# main_schematic.net
KiCad netlist of a schematic drawn in Altium Designer
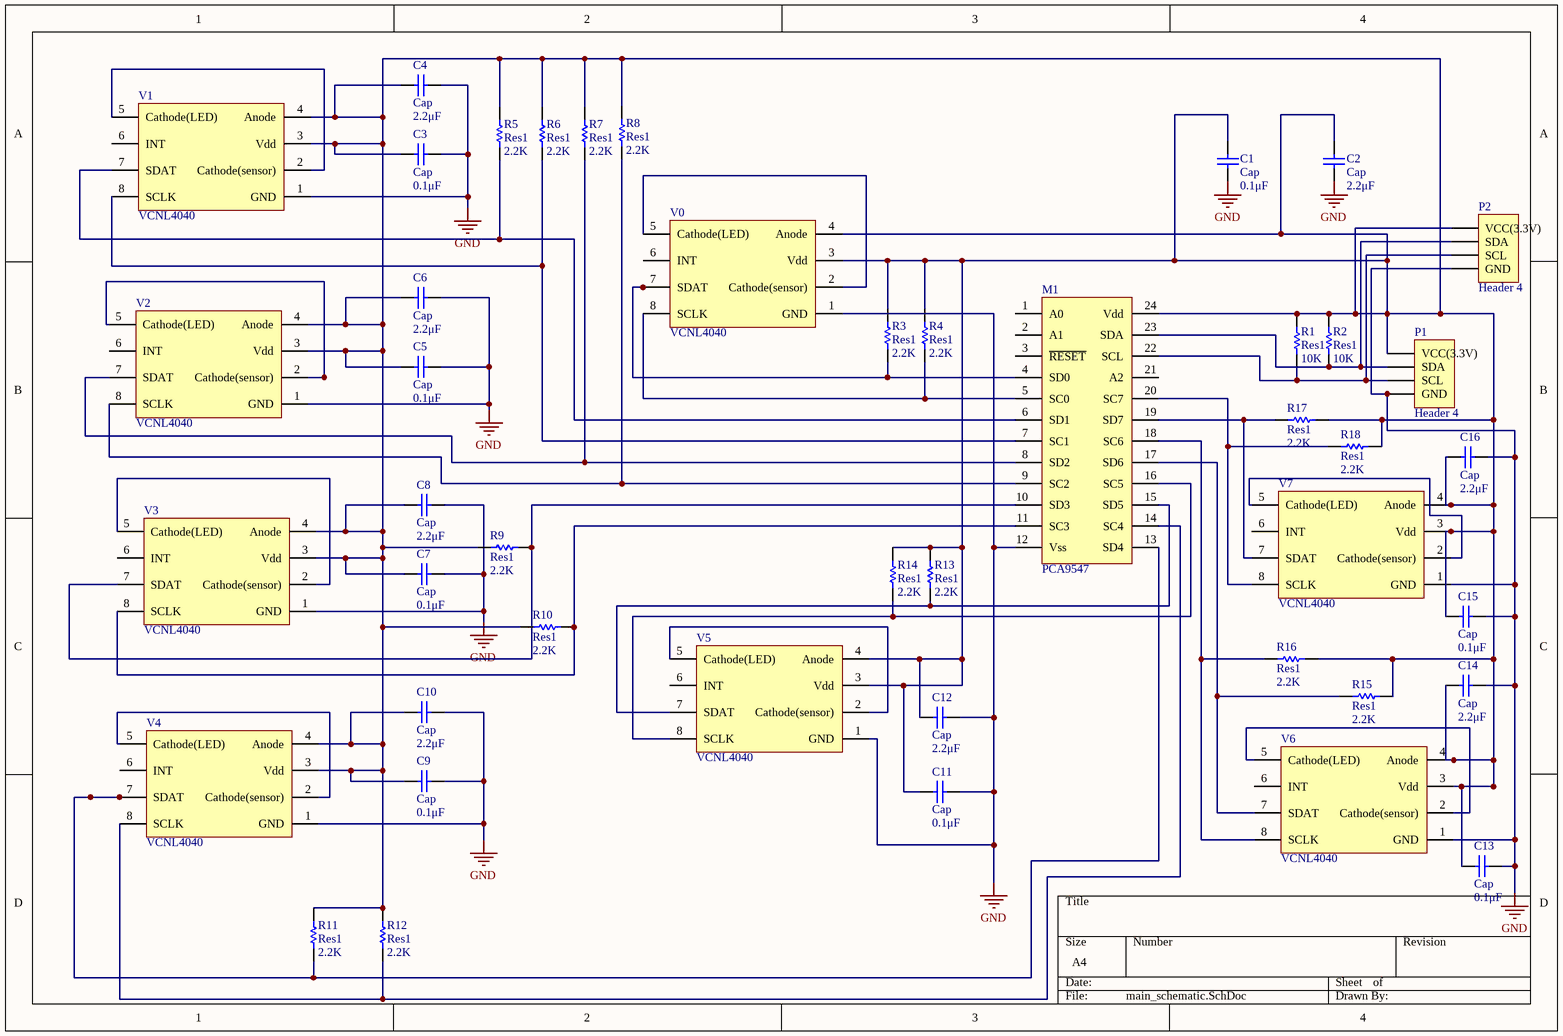
[diagram p0: main_schematic.SchDoc]

(export (version "E")
  (design (tool "Eeschema 10.0.6"))
  (components
    (comp (ref "C1")
      (value "Cap")
      (footprint "1608[0603]")
      (description "Capacitor")
      (fields (field (name "ALTIUM_VALUE") "0.1μF") (field (name "PUBLISHER") "Altium Limited"))
      (libsource (lib "Miscellaneous Devices") (part "Cap"))
    )
    (comp (ref "C2")
      (value "Cap")
      (footprint "1608[0603]")
      (description "Capacitor")
      (fields (field (name "ALTIUM_VALUE") "2.2μF") (field (name "PUBLISHER") "Altium Limited"))
      (libsource (lib "Miscellaneous Devices") (part "Cap"))
    )
    (comp (ref "C3")
      (value "Cap")
      (footprint "1608[0603]")
      (description "Capacitor")
      (fields (field (name "ALTIUM_VALUE") "0.1μF") (field (name "PUBLISHER") "Altium Limited"))
      (libsource (lib "Miscellaneous Devices") (part "Cap"))
    )
    (comp (ref "C4")
      (value "Cap")
      (footprint "1608[0603]")
      (description "Capacitor")
      (fields (field (name "ALTIUM_VALUE") "2.2μF") (field (name "PUBLISHER") "Altium Limited"))
      (libsource (lib "Miscellaneous Devices") (part "Cap"))
    )
    (comp (ref "C5")
      (value "Cap")
      (footprint "1608[0603]")
      (description "Capacitor")
      (fields (field (name "ALTIUM_VALUE") "0.1μF") (field (name "PUBLISHER") "Altium Limited"))
      (libsource (lib "Miscellaneous Devices") (part "Cap"))
    )
    (comp (ref "C6")
      (value "Cap")
      (footprint "1608[0603]")
      (description "Capacitor")
      (fields (field (name "ALTIUM_VALUE") "2.2μF") (field (name "PUBLISHER") "Altium Limited"))
      (libsource (lib "Miscellaneous Devices") (part "Cap"))
    )
    (comp (ref "C7")
      (value "Cap")
      (footprint "1608[0603]")
      (description "Capacitor")
      (fields (field (name "ALTIUM_VALUE") "0.1μF") (field (name "PUBLISHER") "Altium Limited"))
      (libsource (lib "Miscellaneous Devices") (part "Cap"))
    )
    (comp (ref "C8")
      (value "Cap")
      (footprint "1608[0603]")
      (description "Capacitor")
      (fields (field (name "ALTIUM_VALUE") "2.2μF") (field (name "PUBLISHER") "Altium Limited"))
      (libsource (lib "Miscellaneous Devices") (part "Cap"))
    )
    (comp (ref "C9")
      (value "Cap")
      (footprint "1608[0603]")
      (description "Capacitor")
      (fields (field (name "ALTIUM_VALUE") "0.1μF") (field (name "PUBLISHER") "Altium Limited"))
      (libsource (lib "Miscellaneous Devices") (part "Cap"))
    )
    (comp (ref "C10")
      (value "Cap")
      (footprint "1608[0603]")
      (description "Capacitor")
      (fields (field (name "ALTIUM_VALUE") "2.2μF") (field (name "PUBLISHER") "Altium Limited"))
      (libsource (lib "Miscellaneous Devices") (part "Cap"))
    )
    (comp (ref "C11")
      (value "Cap")
      (footprint "1608[0603]")
      (description "Capacitor")
      (fields (field (name "ALTIUM_VALUE") "0.1μF") (field (name "PUBLISHER") "Altium Limited"))
      (libsource (lib "Miscellaneous Devices") (part "Cap"))
    )
    (comp (ref "C12")
      (value "Cap")
      (footprint "1608[0603]")
      (description "Capacitor")
      (fields (field (name "ALTIUM_VALUE") "2.2μF") (field (name "PUBLISHER") "Altium Limited"))
      (libsource (lib "Miscellaneous Devices") (part "Cap"))
    )
    (comp (ref "C13")
      (value "Cap")
      (footprint "1608[0603]")
      (description "Capacitor")
      (fields (field (name "ALTIUM_VALUE") "0.1μF") (field (name "PUBLISHER") "Altium Limited"))
      (libsource (lib "Miscellaneous Devices") (part "Cap"))
    )
    (comp (ref "C14")
      (value "Cap")
      (footprint "1608[0603]")
      (description "Capacitor")
      (fields (field (name "ALTIUM_VALUE") "2.2μF") (field (name "PUBLISHER") "Altium Limited"))
      (libsource (lib "Miscellaneous Devices") (part "Cap"))
    )
    (comp (ref "C15")
      (value "Cap")
      (footprint "1608[0603]")
      (description "Capacitor")
      (fields (field (name "ALTIUM_VALUE") "0.1μF") (field (name "PUBLISHER") "Altium Limited"))
      (libsource (lib "Miscellaneous Devices") (part "Cap"))
    )
    (comp (ref "C16")
      (value "Cap")
      (footprint "1608[0603]")
      (description "Capacitor")
      (fields (field (name "ALTIUM_VALUE") "2.2μF") (field (name "PUBLISHER") "Altium Limited"))
      (libsource (lib "Miscellaneous Devices") (part "Cap"))
    )
    (comp (ref "M1") (value "PCA9547") (footprint "TSSOP24") (libsource (lib "PCA9547") (part "PCA9547")))
    (comp (ref "P1")
      (value "Header 4")
      (footprint "HDR1X4")
      (description "Header, 4-Pin")
      (fields (field (name "PUBLISHER") "Altium Limited"))
      (libsource (lib "Miscellaneous Connectors") (part "Header 4"))
    )
    (comp (ref "P2")
      (value "Header 4")
      (footprint "HDR1X4")
      (description "Header, 4-Pin")
      (fields (field (name "PUBLISHER") "Altium Limited"))
      (libsource (lib "Miscellaneous Connectors") (part "Header 4"))
    )
    (comp (ref "R1")
      (value "Res1")
      (footprint "1608[0603]")
      (description "Resistor")
      (fields (field (name "ALTIUM_VALUE") "10K") (field (name "PUBLISHER") "Altium Limited"))
      (libsource (lib "Miscellaneous Devices") (part "Res1"))
    )
    (comp (ref "R2")
      (value "Res1")
      (footprint "1608[0603]")
      (description "Resistor")
      (fields (field (name "ALTIUM_VALUE") "10K") (field (name "PUBLISHER") "Altium Limited"))
      (libsource (lib "Miscellaneous Devices") (part "Res1"))
    )
    (comp (ref "R3")
      (value "Res1")
      (footprint "1608[0603]")
      (description "Resistor")
      (fields (field (name "ALTIUM_VALUE") "2.2K") (field (name "PUBLISHER") "Altium Limited"))
      (libsource (lib "Miscellaneous Devices") (part "Res1"))
    )
    (comp (ref "R4")
      (value "Res1")
      (footprint "1608[0603]")
      (description "Resistor")
      (fields (field (name "ALTIUM_VALUE") "2.2K") (field (name "PUBLISHER") "Altium Limited"))
      (libsource (lib "Miscellaneous Devices") (part "Res1"))
    )
    (comp (ref "R5")
      (value "Res1")
      (footprint "1608[0603]")
      (description "Resistor")
      (fields (field (name "ALTIUM_VALUE") "2.2K") (field (name "PUBLISHER") "Altium Limited"))
      (libsource (lib "Miscellaneous Devices") (part "Res1"))
    )
    (comp (ref "R6")
      (value "Res1")
      (footprint "1608[0603]")
      (description "Resistor")
      (fields (field (name "ALTIUM_VALUE") "2.2K") (field (name "PUBLISHER") "Altium Limited"))
      (libsource (lib "Miscellaneous Devices") (part "Res1"))
    )
    (comp (ref "R7")
      (value "Res1")
      (footprint "1608[0603]")
      (description "Resistor")
      (fields (field (name "ALTIUM_VALUE") "2.2K") (field (name "PUBLISHER") "Altium Limited"))
      (libsource (lib "Miscellaneous Devices") (part "Res1"))
    )
    (comp (ref "R8")
      (value "Res1")
      (footprint "1608[0603]")
      (description "Resistor")
      (fields (field (name "ALTIUM_VALUE") "2.2K") (field (name "PUBLISHER") "Altium Limited"))
      (libsource (lib "Miscellaneous Devices") (part "Res1"))
    )
    (comp (ref "R9")
      (value "Res1")
      (footprint "1608[0603]")
      (description "Resistor")
      (fields (field (name "ALTIUM_VALUE") "2.2K") (field (name "PUBLISHER") "Altium Limited"))
      (libsource (lib "Miscellaneous Devices") (part "Res1"))
    )
    (comp (ref "R10")
      (value "Res1")
      (footprint "1608[0603]")
      (description "Resistor")
      (fields (field (name "ALTIUM_VALUE") "2.2K") (field (name "PUBLISHER") "Altium Limited"))
      (libsource (lib "Miscellaneous Devices") (part "Res1"))
    )
    (comp (ref "R11")
      (value "Res1")
      (footprint "1608[0603]")
      (description "Resistor")
      (fields (field (name "ALTIUM_VALUE") "2.2K") (field (name "PUBLISHER") "Altium Limited"))
      (libsource (lib "Miscellaneous Devices") (part "Res1"))
    )
    (comp (ref "R12")
      (value "Res1")
      (footprint "1608[0603]")
      (description "Resistor")
      (fields (field (name "ALTIUM_VALUE") "2.2K") (field (name "PUBLISHER") "Altium Limited"))
      (libsource (lib "Miscellaneous Devices") (part "Res1"))
    )
    (comp (ref "R13")
      (value "Res1")
      (footprint "1608[0603]")
      (description "Resistor")
      (fields (field (name "ALTIUM_VALUE") "2.2K") (field (name "PUBLISHER") "Altium Limited"))
      (libsource (lib "Miscellaneous Devices") (part "Res1"))
    )
    (comp (ref "R14")
      (value "Res1")
      (footprint "1608[0603]")
      (description "Resistor")
      (fields (field (name "ALTIUM_VALUE") "2.2K") (field (name "PUBLISHER") "Altium Limited"))
      (libsource (lib "Miscellaneous Devices") (part "Res1"))
    )
    (comp (ref "R15")
      (value "Res1")
      (footprint "1608[0603]")
      (description "Resistor")
      (fields (field (name "ALTIUM_VALUE") "2.2K") (field (name "PUBLISHER") "Altium Limited"))
      (libsource (lib "Miscellaneous Devices") (part "Res1"))
    )
    (comp (ref "R16")
      (value "Res1")
      (footprint "1608[0603]")
      (description "Resistor")
      (fields (field (name "ALTIUM_VALUE") "2.2K") (field (name "PUBLISHER") "Altium Limited"))
      (libsource (lib "Miscellaneous Devices") (part "Res1"))
    )
    (comp (ref "R17")
      (value "Res1")
      (footprint "1608[0603]")
      (description "Resistor")
      (fields (field (name "ALTIUM_VALUE") "2.2K") (field (name "PUBLISHER") "Altium Limited"))
      (libsource (lib "Miscellaneous Devices") (part "Res1"))
    )
    (comp (ref "R18")
      (value "Res1")
      (footprint "1608[0603]")
      (description "Resistor")
      (fields (field (name "ALTIUM_VALUE") "2.2K") (field (name "PUBLISHER") "Altium Limited"))
      (libsource (lib "Miscellaneous Devices") (part "Res1"))
    )
    (comp (ref "V0") (value "VCNL4040") (footprint "SOP8") (libsource (lib "VCNL4040") (part "Component_1")))
    (comp (ref "V1") (value "VCNL4040") (footprint "SOP8") (libsource (lib "VCNL4040") (part "Component_1")))
    (comp (ref "V2") (value "VCNL4040") (footprint "SOP8") (libsource (lib "VCNL4040") (part "Component_1")))
    (comp (ref "V3") (value "VCNL4040") (footprint "SOP8") (libsource (lib "VCNL4040") (part "Component_1")))
    (comp (ref "V4") (value "VCNL4040") (footprint "SOP8") (libsource (lib "VCNL4040") (part "Component_1")))
    (comp (ref "V5") (value "VCNL4040") (footprint "SOP8") (libsource (lib "VCNL4040") (part "Component_1")))
    (comp (ref "V6") (value "VCNL4040") (footprint "SOP8") (libsource (lib "VCNL4040") (part "Component_1")))
    (comp (ref "V7") (value "VCNL4040") (footprint "SOP8") (libsource (lib "VCNL4040") (part "Component_1")))
  )
  (nets
    (net (code "1") (name "GND") (class "Default")
      (node (ref "C1") (pin "1") (pinfunction "1_1") (pintype "passive"))
      (node (ref "C10") (pin "1") (pinfunction "1_1") (pintype "passive"))
      (node (ref "C11") (pin "1") (pinfunction "1_1") (pintype "passive"))
      (node (ref "C12") (pin "1") (pinfunction "1_1") (pintype "passive"))
      (node (ref "C13") (pin "1") (pinfunction "1_1") (pintype "passive"))
      (node (ref "C14") (pin "1") (pinfunction "1_1") (pintype "passive"))
      (node (ref "C15") (pin "1") (pinfunction "1_1") (pintype "passive"))
      (node (ref "C16") (pin "1") (pinfunction "1_1") (pintype "passive"))
      (node (ref "C2") (pin "1") (pinfunction "1_1") (pintype "passive"))
      (node (ref "C3") (pin "1") (pinfunction "1_1") (pintype "passive"))
      (node (ref "C4") (pin "1") (pinfunction "1_1") (pintype "passive"))
      (node (ref "C5") (pin "1") (pinfunction "1_1") (pintype "passive"))
      (node (ref "C6") (pin "1") (pinfunction "1_1") (pintype "passive"))
      (node (ref "C7") (pin "1") (pinfunction "1_1") (pintype "passive"))
      (node (ref "C8") (pin "1") (pinfunction "1_1") (pintype "passive"))
      (node (ref "C9") (pin "1") (pinfunction "1_1") (pintype "passive"))
      (node (ref "M1") (pin "12") (pinfunction "Vss_12") (pintype "passive"))
      (node (ref "P1") (pin "4") (pinfunction "GND_4") (pintype "power_in"))
      (node (ref "P2") (pin "4") (pinfunction "GND_4") (pintype "power_in"))
      (node (ref "V0") (pin "1") (pinfunction "GND_1") (pintype "passive"))
      (node (ref "V1") (pin "1") (pinfunction "GND_1") (pintype "passive"))
      (node (ref "V2") (pin "1") (pinfunction "GND_1") (pintype "passive"))
      (node (ref "V3") (pin "1") (pinfunction "GND_1") (pintype "passive"))
      (node (ref "V4") (pin "1") (pinfunction "GND_1") (pintype "passive"))
      (node (ref "V5") (pin "1") (pinfunction "GND_1") (pintype "passive"))
      (node (ref "V6") (pin "1") (pinfunction "GND_1") (pintype "passive"))
      (node (ref "V7") (pin "1") (pinfunction "GND_1") (pintype "passive"))
    )
    (net (code "2") (name "Net-(M1-SC0)") (class "Default")
      (node (ref "M1") (pin "5") (pinfunction "SC0_5") (pintype "passive"))
      (node (ref "R4") (pin "1") (pinfunction "1_1") (pintype "passive"))
      (node (ref "V0") (pin "8") (pinfunction "SCLK_8") (pintype "passive"))
    )
    (net (code "3") (name "Net-(M1-SC1)") (class "Default")
      (node (ref "M1") (pin "7") (pinfunction "SC1_7") (pintype "passive"))
      (node (ref "R6") (pin "1") (pinfunction "1_1") (pintype "passive"))
      (node (ref "V1") (pin "8") (pinfunction "SCLK_8") (pintype "passive"))
    )
    (net (code "4") (name "Net-(M1-SC2)") (class "Default")
      (node (ref "M1") (pin "9") (pinfunction "SC2_9") (pintype "passive"))
      (node (ref "R8") (pin "1") (pinfunction "1_1") (pintype "passive"))
      (node (ref "V2") (pin "8") (pinfunction "SCLK_8") (pintype "passive"))
    )
    (net (code "5") (name "Net-(M1-SC3)") (class "Default")
      (node (ref "M1") (pin "11") (pinfunction "SC3_11") (pintype "passive"))
      (node (ref "R10") (pin "1") (pinfunction "1_1") (pintype "passive"))
      (node (ref "V3") (pin "8") (pinfunction "SCLK_8") (pintype "passive"))
    )
    (net (code "6") (name "Net-(M1-SC4)") (class "Default")
      (node (ref "M1") (pin "14") (pinfunction "SC4_14") (pintype "passive"))
      (node (ref "R12") (pin "2") (pinfunction "2_2") (pintype "passive"))
      (node (ref "V4") (pin "8") (pinfunction "SCLK_8") (pintype "passive"))
    )
    (net (code "7") (name "Net-(M1-SC5)") (class "Default")
      (node (ref "M1") (pin "16") (pinfunction "SC5_16") (pintype "passive"))
      (node (ref "R14") (pin "1") (pinfunction "1_1") (pintype "passive"))
      (node (ref "V5") (pin "8") (pinfunction "SCLK_8") (pintype "passive"))
    )
    (net (code "8") (name "Net-(M1-SC6)") (class "Default")
      (node (ref "M1") (pin "18") (pinfunction "SC6_18") (pintype "passive"))
      (node (ref "R16") (pin "2") (pinfunction "2_2") (pintype "passive"))
      (node (ref "V6") (pin "8") (pinfunction "SCLK_8") (pintype "passive"))
    )
    (net (code "9") (name "Net-(M1-SC7)") (class "Default")
      (node (ref "M1") (pin "20") (pinfunction "SC7_20") (pintype "passive"))
      (node (ref "R18") (pin "2") (pinfunction "2_2") (pintype "passive"))
      (node (ref "V7") (pin "8") (pinfunction "SCLK_8") (pintype "passive"))
    )
    (net (code "10") (name "Net-(M1-SCL)") (class "Default")
      (node (ref "M1") (pin "22") (pinfunction "SCL_22") (pintype "passive"))
      (node (ref "P1") (pin "3") (pinfunction "SCL_3") (pintype "passive"))
      (node (ref "P2") (pin "3") (pinfunction "SCL_3") (pintype "passive"))
      (node (ref "R1") (pin "1") (pinfunction "1_1") (pintype "passive"))
    )
    (net (code "11") (name "Net-(M1-SD0)") (class "Default")
      (node (ref "M1") (pin "4") (pinfunction "SD0_4") (pintype "passive"))
      (node (ref "R3") (pin "1") (pinfunction "1_1") (pintype "passive"))
      (node (ref "V0") (pin "7") (pinfunction "SDAT_7") (pintype "passive"))
    )
    (net (code "12") (name "Net-(M1-SD1)") (class "Default")
      (node (ref "M1") (pin "6") (pinfunction "SD1_6") (pintype "passive"))
      (node (ref "R5") (pin "1") (pinfunction "1_1") (pintype "passive"))
      (node (ref "V1") (pin "7") (pinfunction "SDAT_7") (pintype "passive"))
    )
    (net (code "13") (name "Net-(M1-SD2)") (class "Default")
      (node (ref "M1") (pin "8") (pinfunction "SD2_8") (pintype "passive"))
      (node (ref "R7") (pin "1") (pinfunction "1_1") (pintype "passive"))
      (node (ref "V2") (pin "7") (pinfunction "SDAT_7") (pintype "passive"))
    )
    (net (code "14") (name "Net-(M1-SD3)") (class "Default")
      (node (ref "M1") (pin "10") (pinfunction "SD3_10") (pintype "passive"))
      (node (ref "R9") (pin "1") (pinfunction "1_1") (pintype "passive"))
      (node (ref "V3") (pin "7") (pinfunction "SDAT_7") (pintype "passive"))
    )
    (net (code "15") (name "Net-(M1-SD4)") (class "Default")
      (node (ref "M1") (pin "13") (pinfunction "SD4_13") (pintype "passive"))
      (node (ref "R11") (pin "2") (pinfunction "2_2") (pintype "passive"))
      (node (ref "V4") (pin "7") (pinfunction "SDAT_7") (pintype "passive"))
    )
    (net (code "16") (name "Net-(M1-SD5)") (class "Default")
      (node (ref "M1") (pin "15") (pinfunction "SD5_15") (pintype "passive"))
      (node (ref "R13") (pin "1") (pinfunction "1_1") (pintype "passive"))
      (node (ref "V5") (pin "7") (pinfunction "SDAT_7") (pintype "passive"))
    )
    (net (code "17") (name "Net-(M1-SD6)") (class "Default")
      (node (ref "M1") (pin "17") (pinfunction "SD6_17") (pintype "passive"))
      (node (ref "R15") (pin "2") (pinfunction "2_2") (pintype "passive"))
      (node (ref "V6") (pin "7") (pinfunction "SDAT_7") (pintype "passive"))
    )
    (net (code "18") (name "Net-(M1-SD7)") (class "Default")
      (node (ref "M1") (pin "19") (pinfunction "SD7_19") (pintype "passive"))
      (node (ref "R17") (pin "2") (pinfunction "2_2") (pintype "passive"))
      (node (ref "V7") (pin "7") (pinfunction "SDAT_7") (pintype "passive"))
    )
    (net (code "19") (name "Net-(M1-SDA)") (class "Default")
      (node (ref "M1") (pin "23") (pinfunction "SDA_23") (pintype "passive"))
      (node (ref "P1") (pin "2") (pinfunction "SDA_2") (pintype "passive"))
      (node (ref "P2") (pin "2") (pinfunction "SDA_2") (pintype "passive"))
      (node (ref "R2") (pin "1") (pinfunction "1_1") (pintype "passive"))
    )
    (net (code "20") (name "Net-(M1-Vdd)") (class "Default")
      (node (ref "C1") (pin "2") (pinfunction "2_2") (pintype "passive"))
      (node (ref "C10") (pin "2") (pinfunction "2_2") (pintype "passive"))
      (node (ref "C11") (pin "2") (pinfunction "2_2") (pintype "passive"))
      (node (ref "C12") (pin "2") (pinfunction "2_2") (pintype "passive"))
      (node (ref "C13") (pin "2") (pinfunction "2_2") (pintype "passive"))
      (node (ref "C14") (pin "2") (pinfunction "2_2") (pintype "passive"))
      (node (ref "C15") (pin "2") (pinfunction "2_2") (pintype "passive"))
      (node (ref "C16") (pin "2") (pinfunction "2_2") (pintype "passive"))
      (node (ref "C2") (pin "2") (pinfunction "2_2") (pintype "passive"))
      (node (ref "C3") (pin "2") (pinfunction "2_2") (pintype "passive"))
      (node (ref "C4") (pin "2") (pinfunction "2_2") (pintype "passive"))
      (node (ref "C5") (pin "2") (pinfunction "2_2") (pintype "passive"))
      (node (ref "C6") (pin "2") (pinfunction "2_2") (pintype "passive"))
      (node (ref "C7") (pin "2") (pinfunction "2_2") (pintype "passive"))
      (node (ref "C8") (pin "2") (pinfunction "2_2") (pintype "passive"))
      (node (ref "C9") (pin "2") (pinfunction "2_2") (pintype "passive"))
      (node (ref "M1") (pin "24") (pinfunction "Vdd_24") (pintype "passive"))
      (node (ref "P1") (pin "1") (pinfunction "VCC(3.3V)_1") (pintype "power_in"))
      (node (ref "P2") (pin "1") (pinfunction "VCC(3.3V)_1") (pintype "power_in"))
      (node (ref "R1") (pin "2") (pinfunction "2_2") (pintype "passive"))
      (node (ref "R10") (pin "2") (pinfunction "2_2") (pintype "passive"))
      (node (ref "R11") (pin "1") (pinfunction "1_1") (pintype "passive"))
      (node (ref "R12") (pin "1") (pinfunction "1_1") (pintype "passive"))
      (node (ref "R13") (pin "2") (pinfunction "2_2") (pintype "passive"))
      (node (ref "R14") (pin "2") (pinfunction "2_2") (pintype "passive"))
      (node (ref "R15") (pin "1") (pinfunction "1_1") (pintype "passive"))
      (node (ref "R16") (pin "1") (pinfunction "1_1") (pintype "passive"))
      (node (ref "R17") (pin "1") (pinfunction "1_1") (pintype "passive"))
      (node (ref "R18") (pin "1") (pinfunction "1_1") (pintype "passive"))
      (node (ref "R2") (pin "2") (pinfunction "2_2") (pintype "passive"))
      (node (ref "R3") (pin "2") (pinfunction "2_2") (pintype "passive"))
      (node (ref "R4") (pin "2") (pinfunction "2_2") (pintype "passive"))
      (node (ref "R5") (pin "2") (pinfunction "2_2") (pintype "passive"))
      (node (ref "R6") (pin "2") (pinfunction "2_2") (pintype "passive"))
      (node (ref "R7") (pin "2") (pinfunction "2_2") (pintype "passive"))
      (node (ref "R8") (pin "2") (pinfunction "2_2") (pintype "passive"))
      (node (ref "R9") (pin "2") (pinfunction "2_2") (pintype "passive"))
      (node (ref "V0") (pin "3") (pinfunction "Vdd_3") (pintype "passive"))
      (node (ref "V0") (pin "4") (pinfunction "Anode_4") (pintype "passive"))
      (node (ref "V1") (pin "3") (pinfunction "Vdd_3") (pintype "passive"))
      (node (ref "V1") (pin "4") (pinfunction "Anode_4") (pintype "passive"))
      (node (ref "V2") (pin "3") (pinfunction "Vdd_3") (pintype "passive"))
      (node (ref "V2") (pin "4") (pinfunction "Anode_4") (pintype "passive"))
      (node (ref "V3") (pin "3") (pinfunction "Vdd_3") (pintype "passive"))
      (node (ref "V3") (pin "4") (pinfunction "Anode_4") (pintype "passive"))
      (node (ref "V4") (pin "3") (pinfunction "Vdd_3") (pintype "passive"))
      (node (ref "V4") (pin "4") (pinfunction "Anode_4") (pintype "passive"))
      (node (ref "V5") (pin "3") (pinfunction "Vdd_3") (pintype "passive"))
      (node (ref "V5") (pin "4") (pinfunction "Anode_4") (pintype "passive"))
      (node (ref "V6") (pin "3") (pinfunction "Vdd_3") (pintype "passive"))
      (node (ref "V6") (pin "4") (pinfunction "Anode_4") (pintype "passive"))
      (node (ref "V7") (pin "3") (pinfunction "Vdd_3") (pintype "passive"))
      (node (ref "V7") (pin "4") (pinfunction "Anode_4") (pintype "passive"))
    )
    (net (code "21") (name "Net-(V0-Cathode(LED))") (class "Default")
      (node (ref "V0") (pin "2") (pinfunction "Cathode(sensor)_2") (pintype "passive"))
      (node (ref "V0") (pin "5") (pinfunction "Cathode(LED)_5") (pintype "passive"))
    )
    (net (code "22") (name "Net-(V1-Cathode(LED))") (class "Default")
      (node (ref "V1") (pin "2") (pinfunction "Cathode(sensor)_2") (pintype "passive"))
      (node (ref "V1") (pin "5") (pinfunction "Cathode(LED)_5") (pintype "passive"))
    )
    (net (code "23") (name "Net-(V2-Cathode(LED))") (class "Default")
      (node (ref "V2") (pin "2") (pinfunction "Cathode(sensor)_2") (pintype "passive"))
      (node (ref "V2") (pin "5") (pinfunction "Cathode(LED)_5") (pintype "passive"))
    )
    (net (code "24") (name "Net-(V3-Cathode(LED))") (class "Default")
      (node (ref "V3") (pin "2") (pinfunction "Cathode(sensor)_2") (pintype "passive"))
      (node (ref "V3") (pin "5") (pinfunction "Cathode(LED)_5") (pintype "passive"))
    )
    (net (code "25") (name "Net-(V4-Cathode(LED))") (class "Default")
      (node (ref "V4") (pin "2") (pinfunction "Cathode(sensor)_2") (pintype "passive"))
      (node (ref "V4") (pin "5") (pinfunction "Cathode(LED)_5") (pintype "passive"))
    )
    (net (code "26") (name "Net-(V5-Cathode(LED))") (class "Default")
      (node (ref "V5") (pin "2") (pinfunction "Cathode(sensor)_2") (pintype "passive"))
      (node (ref "V5") (pin "5") (pinfunction "Cathode(LED)_5") (pintype "passive"))
    )
    (net (code "27") (name "Net-(V6-Cathode(LED))") (class "Default")
      (node (ref "V6") (pin "2") (pinfunction "Cathode(sensor)_2") (pintype "passive"))
      (node (ref "V6") (pin "5") (pinfunction "Cathode(LED)_5") (pintype "passive"))
    )
    (net (code "28") (name "Net-(V7-Cathode(LED))") (class "Default")
      (node (ref "V7") (pin "2") (pinfunction "Cathode(sensor)_2") (pintype "passive"))
      (node (ref "V7") (pin "5") (pinfunction "Cathode(LED)_5") (pintype "passive"))
    )
    (net (code "29") (name "unconnected-(M1-A0-Pad1)") (class "Default")
      (node (ref "M1") (pin "1") (pinfunction "A0_1") (pintype "passive"))
    )
    (net (code "30") (name "unconnected-(M1-A1-Pad2)") (class "Default")
      (node (ref "M1") (pin "2") (pinfunction "A1_2") (pintype "passive"))
    )
    (net (code "31") (name "unconnected-(M1-A2-Pad21)") (class "Default")
      (node (ref "M1") (pin "21") (pinfunction "A2_21") (pintype "passive"))
    )
    (net (code "32") (name "unconnected-(M1-~{RESET}-Pad3)") (class "Default")
      (node (ref "M1") (pin "3") (pinfunction "~{RESET}_3") (pintype "passive"))
    )
    (net (code "33") (name "unconnected-(V0-INT-Pad6)") (class "Default")
      (node (ref "V0") (pin "6") (pinfunction "INT_6") (pintype "passive"))
    )
    (net (code "34") (name "unconnected-(V1-INT-Pad6)") (class "Default")
      (node (ref "V1") (pin "6") (pinfunction "INT_6") (pintype "passive"))
    )
    (net (code "35") (name "unconnected-(V2-INT-Pad6)") (class "Default")
      (node (ref "V2") (pin "6") (pinfunction "INT_6") (pintype "passive"))
    )
    (net (code "36") (name "unconnected-(V3-INT-Pad6)") (class "Default")
      (node (ref "V3") (pin "6") (pinfunction "INT_6") (pintype "passive"))
    )
    (net (code "37") (name "unconnected-(V4-INT-Pad6)") (class "Default")
      (node (ref "V4") (pin "6") (pinfunction "INT_6") (pintype "passive"))
    )
    (net (code "38") (name "unconnected-(V5-INT-Pad6)") (class "Default")
      (node (ref "V5") (pin "6") (pinfunction "INT_6") (pintype "passive"))
    )
    (net (code "39") (name "unconnected-(V6-INT-Pad6)") (class "Default")
      (node (ref "V6") (pin "6") (pinfunction "INT_6") (pintype "passive"))
    )
    (net (code "40") (name "unconnected-(V7-INT-Pad6)") (class "Default")
      (node (ref "V7") (pin "6") (pinfunction "INT_6") (pintype "passive"))
    )
  )
)
